# FPA.net
KiCad netlist of a schematic drawn in Altium Designer
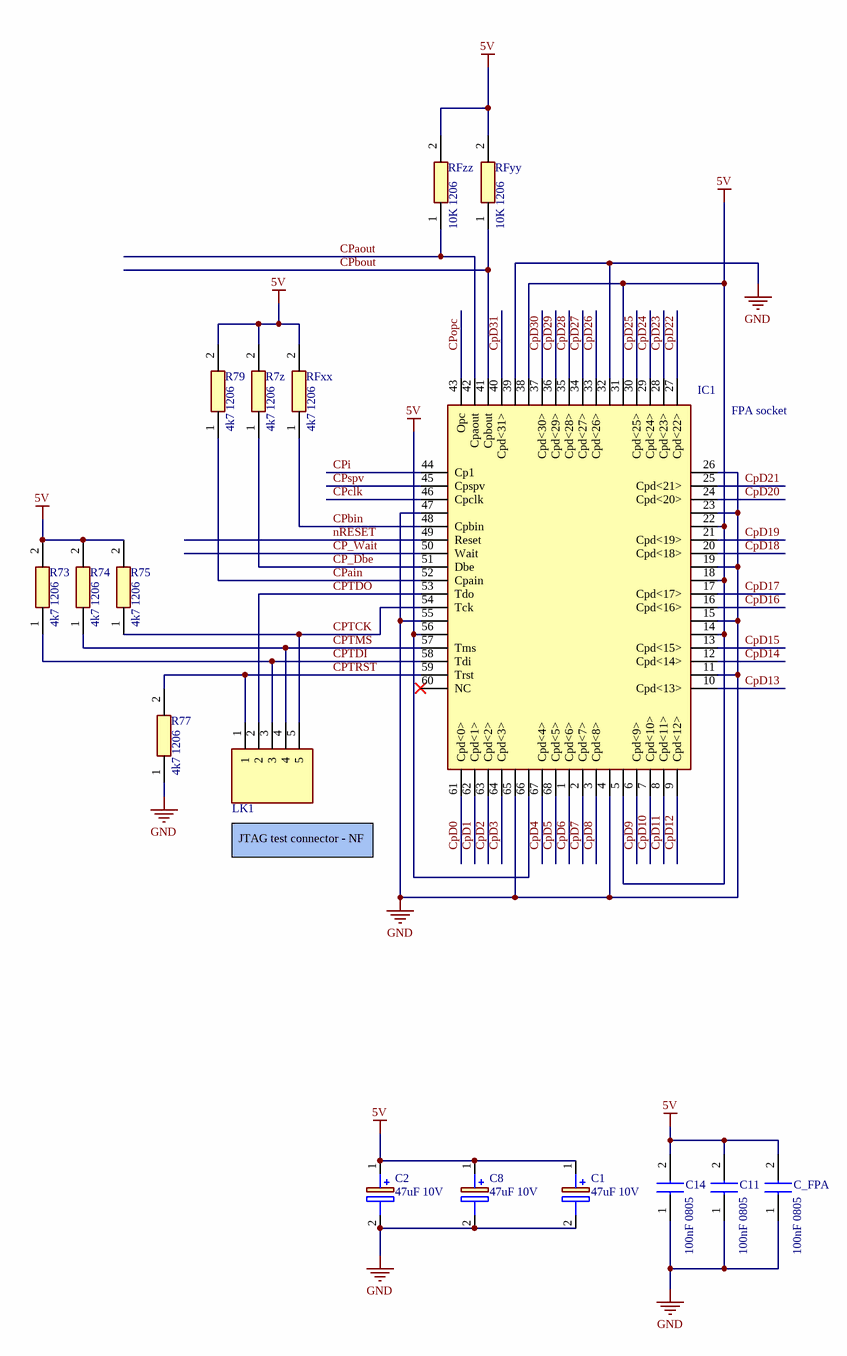
[diagram p0: FPA.SchDoc]

(export (version "E")
  (design (tool "Eeschema 10.0.6"))
  (components
    (comp (ref "C1")
      (value "47uF 10V")
      (footprint "SamacSys:CAPPA3500W50L1400D525")
      (description "Capacitor Polarised")
      (fields
        (field (name "MANUFACTURER_PART_NUMBER") "226TTA035MSD")
        (field (name "MOUSER PART NUMBER") "598-226TTA035MSD")
      )
      (libsource (lib "*") (part "226TTA035MSD"))
    )
    (comp (ref "C2")
      (value "47uF 10V")
      (footprint "SamacSys:CAPPA3500W50L1400D525")
      (description "Capacitor Polarised")
      (fields
        (field (name "MANUFACTURER_PART_NUMBER") "226TTA035MSD")
        (field (name "MOUSER PART NUMBER") "598-226TTA035MSD")
      )
      (libsource (lib "*") (part "226TTA035MSD"))
    )
    (comp (ref "C8")
      (value "47uF 10V")
      (footprint "SamacSys:CAPPA3500W50L1400D525")
      (description "Capacitor Polarised")
      (fields
        (field (name "MANUFACTURER_PART_NUMBER") "226TTA035MSD")
        (field (name "MOUSER PART NUMBER") "598-226TTA035MSD")
      )
      (libsource (lib "*") (part "226TTA035MSD"))
    )
    (comp (ref "C11")
      (value "100nF 0805")
      (footprint "SamacSys:CAPC2012X140N")
      (description "Capacitor")
      (fields
        (field (name "MANUFACTURER_PART_NUMBER") "C0805C104J4JACAUTO")
        (field (name "MOUSER PART NUMBER") "80-C0805C104J4JAUTO")
      )
      (libsource (lib "*") (part "C0805C104J4JACAUTO"))
    )
    (comp (ref "C14")
      (value "100nF 0805")
      (footprint "SamacSys:CAPC2012X140N")
      (description "Capacitor")
      (fields
        (field (name "MANUFACTURER_PART_NUMBER") "C0805C104J4JACAUTO")
        (field (name "MOUSER PART NUMBER") "80-C0805C104J4JAUTO")
      )
      (libsource (lib "*") (part "C0805C104J4JACAUTO"))
    )
    (comp (ref "C_FPA")
      (value "100nF 0805")
      (footprint "SamacSys:CAPC2012X140N")
      (description "Capacitor")
      (fields
        (field (name "MANUFACTURER_PART_NUMBER") "C0805C104J4JACAUTO")
        (field (name "MOUSER PART NUMBER") "80-C0805C104J4JAUTO")
      )
      (libsource (lib "*") (part "C0805C104J4JACAUTO"))
    )
    (comp (ref "IC1")
      (value "FPA socket")
      (footprint "PLCC68ATx")
      (fields
        (field (name "MANUFACTURER_PART_NUMBER") "8468-21B1-RK-TR")
        (field (name "MOUSER PART NUMBER") "517-8468-21B1-RK-TR")
      )
      (libsource (lib "Acorn") (part "FPA_SKT_THT"))
    )
    (comp (ref "LK1")
      (value "PREC005SAAN-RC")
      (footprint "SamacSys:HDRV5W64P0X254_1X5_1270X254X864P")
      (description "Connector")
      (libsource (lib "*") (part "PREC005SAAN-RC"))
    )
    (comp (ref "R7z")
      (value "4k7 1206")
      (footprint "SamacSys:ERJ8ENF1000V")
      (description "Resistor")
      (fields
        (field (name "MANUFACTURER_PART_NUMBER") "ERJ-8ENF4701V")
        (field (name "MOUSER PART NUMBER") "667-ERJ-8ENF4701V")
      )
      (libsource (lib "*") (part "ERJ-8ENF4701V"))
    )
    (comp (ref "R73")
      (value "4k7 1206")
      (footprint "SamacSys:ERJ8ENF1000V")
      (description "Resistor")
      (fields
        (field (name "MANUFACTURER_PART_NUMBER") "ERJ-8ENF4701V")
        (field (name "MOUSER PART NUMBER") "667-ERJ-8ENF4701V")
      )
      (libsource (lib "*") (part "ERJ-8ENF4701V"))
    )
    (comp (ref "R74")
      (value "4k7 1206")
      (footprint "SamacSys:ERJ8ENF1000V")
      (description "Resistor")
      (fields
        (field (name "MANUFACTURER_PART_NUMBER") "ERJ-8ENF4701V")
        (field (name "MOUSER PART NUMBER") "667-ERJ-8ENF4701V")
      )
      (libsource (lib "*") (part "ERJ-8ENF4701V"))
    )
    (comp (ref "R75")
      (value "4k7 1206")
      (footprint "SamacSys:ERJ8ENF1000V")
      (description "Resistor")
      (fields
        (field (name "MANUFACTURER_PART_NUMBER") "ERJ-8ENF4701V")
        (field (name "MOUSER PART NUMBER") "667-ERJ-8ENF4701V")
      )
      (libsource (lib "*") (part "ERJ-8ENF4701V"))
    )
    (comp (ref "R77")
      (value "4k7 1206")
      (footprint "SamacSys:ERJ8ENF1000V")
      (description "Resistor")
      (fields
        (field (name "MANUFACTURER_PART_NUMBER") "ERJ-8ENF4701V")
        (field (name "MOUSER PART NUMBER") "667-ERJ-8ENF4701V")
      )
      (libsource (lib "*") (part "ERJ-8ENF4701V"))
    )
    (comp (ref "R79")
      (value "4k7 1206")
      (footprint "SamacSys:ERJ8ENF1000V")
      (description "Resistor")
      (fields
        (field (name "MANUFACTURER_PART_NUMBER") "ERJ-8ENF4701V")
        (field (name "MOUSER PART NUMBER") "667-ERJ-8ENF4701V")
      )
      (libsource (lib "*") (part "ERJ-8ENF4701V"))
    )
    (comp (ref "RFxx")
      (value "4k7 1206")
      (footprint "SamacSys:ERJ8ENF1000V")
      (description "Resistor")
      (fields
        (field (name "MANUFACTURER_PART_NUMBER") "ERJ-8ENF4701V")
        (field (name "MOUSER PART NUMBER") "667-ERJ-8ENF4701V")
      )
      (libsource (lib "*") (part "ERJ-8ENF4701V"))
    )
    (comp (ref "RFyy")
      (value "10K 1206")
      (footprint "SamacSys:ERJUP8")
      (description "Resistor")
      (fields (field (name "MANUFACTURER_PART_NUMBER") "ERJ-UP8D1002V"))
      (libsource (lib "*") (part "ERJ-UP8D1002V"))
    )
    (comp (ref "RFzz")
      (value "10K 1206")
      (footprint "SamacSys:ERJUP8")
      (description "Resistor")
      (fields (field (name "MANUFACTURER_PART_NUMBER") "ERJ-UP8D1002V"))
      (libsource (lib "*") (part "ERJ-UP8D1002V"))
    )
  )
  (nets
    (net (code "1") (name "/CPTCK") (class "Default")
      (node (ref "IC1") (pin "54") (pinfunction "Tck_54") (pintype "passive"))
      (node (ref "LK1") (pin "5") (pinfunction "5_5") (pintype "passive"))
      (node (ref "R75") (pin "1") (pinfunction "1_1") (pintype "passive"))
    )
    (net (code "2") (name "/CPTDI") (class "Default")
      (node (ref "IC1") (pin "58") (pinfunction "Tdi_58") (pintype "passive"))
      (node (ref "LK1") (pin "3") (pinfunction "3_3") (pintype "passive"))
      (node (ref "R73") (pin "1") (pinfunction "1_1") (pintype "passive"))
    )
    (net (code "3") (name "/CPTDO") (class "Default")
      (node (ref "IC1") (pin "53") (pinfunction "Tdo_53") (pintype "passive"))
      (node (ref "LK1") (pin "2") (pinfunction "2_2") (pintype "passive"))
    )
    (net (code "4") (name "/CPTMS") (class "Default")
      (node (ref "IC1") (pin "57") (pinfunction "Tms_57") (pintype "passive"))
      (node (ref "LK1") (pin "4") (pinfunction "4_4") (pintype "passive"))
      (node (ref "R74") (pin "1") (pinfunction "1_1") (pintype "passive"))
    )
    (net (code "5") (name "/CPTRST") (class "Default")
      (node (ref "IC1") (pin "59") (pinfunction "Trst_59") (pintype "passive"))
      (node (ref "LK1") (pin "1") (pinfunction "1_1") (pintype "passive"))
      (node (ref "R77") (pin "2") (pinfunction "2_2") (pintype "passive"))
    )
    (net (code "6") (name "/CP_Dbe") (class "Default")
      (node (ref "IC1") (pin "51") (pinfunction "Dbe_51") (pintype "passive"))
      (node (ref "R7z") (pin "1") (pinfunction "1_1") (pintype "passive"))
    )
    (net (code "7") (name "/CP_Wait") (class "Default")
      (node (ref "IC1") (pin "50") (pinfunction "Wait_50") (pintype "passive"))
    )
    (net (code "8") (name "/CPain") (class "Default")
      (node (ref "IC1") (pin "52") (pinfunction "Cpain_52") (pintype "passive"))
      (node (ref "R79") (pin "1") (pinfunction "1_1") (pintype "passive"))
    )
    (net (code "9") (name "/CPaout") (class "Default")
      (node (ref "IC1") (pin "42") (pinfunction "Cpaout_42") (pintype "passive"))
      (node (ref "RFzz") (pin "1") (pinfunction "1_1") (pintype "passive"))
    )
    (net (code "10") (name "/CPbin") (class "Default")
      (node (ref "IC1") (pin "48") (pinfunction "Cpbin_48") (pintype "passive"))
      (node (ref "RFxx") (pin "1") (pinfunction "1_1") (pintype "passive"))
    )
    (net (code "11") (name "/CPbout") (class "Default")
      (node (ref "IC1") (pin "41") (pinfunction "Cpbout_41") (pintype "passive"))
      (node (ref "RFyy") (pin "1") (pinfunction "1_1") (pintype "passive"))
    )
    (net (code "12") (name "/CPclk") (class "Default")
      (node (ref "IC1") (pin "46") (pinfunction "Cpclk_46") (pintype "passive"))
    )
    (net (code "13") (name "/CPi") (class "Default")
      (node (ref "IC1") (pin "44") (pinfunction "Cp1_44") (pintype "passive"))
    )
    (net (code "14") (name "/CPopc") (class "Default")
      (node (ref "IC1") (pin "43") (pinfunction "Opc_43") (pintype "passive"))
    )
    (net (code "15") (name "/CPspv") (class "Default")
      (node (ref "IC1") (pin "45") (pinfunction "Cpspv_45") (pintype "passive"))
    )
    (net (code "16") (name "/CpD0") (class "Default")
      (node (ref "IC1") (pin "61") (pinfunction "Cpd<0>_61") (pintype "passive"))
    )
    (net (code "17") (name "/CpD1") (class "Default")
      (node (ref "IC1") (pin "62") (pinfunction "Cpd<1>_62") (pintype "passive"))
    )
    (net (code "18") (name "/CpD2") (class "Default")
      (node (ref "IC1") (pin "63") (pinfunction "Cpd<2>_63") (pintype "passive"))
    )
    (net (code "19") (name "/CpD3") (class "Default")
      (node (ref "IC1") (pin "64") (pinfunction "Cpd<3>_64") (pintype "passive"))
    )
    (net (code "20") (name "/CpD4") (class "Default")
      (node (ref "IC1") (pin "67") (pinfunction "Cpd<4>_67") (pintype "passive"))
    )
    (net (code "21") (name "/CpD5") (class "Default")
      (node (ref "IC1") (pin "68") (pinfunction "Cpd<5>_68") (pintype "passive"))
    )
    (net (code "22") (name "/CpD6") (class "Default")
      (node (ref "IC1") (pin "1") (pinfunction "Cpd<6>_1") (pintype "passive"))
    )
    (net (code "23") (name "/CpD7") (class "Default")
      (node (ref "IC1") (pin "2") (pinfunction "Cpd<7>_2") (pintype "passive"))
    )
    (net (code "24") (name "/CpD8") (class "Default")
      (node (ref "IC1") (pin "3") (pinfunction "Cpd<8>_3") (pintype "passive"))
    )
    (net (code "25") (name "/CpD9") (class "Default")
      (node (ref "IC1") (pin "6") (pinfunction "Cpd<9>_6") (pintype "passive"))
    )
    (net (code "26") (name "/CpD10") (class "Default")
      (node (ref "IC1") (pin "7") (pinfunction "Cpd<10>_7") (pintype "passive"))
    )
    (net (code "27") (name "/CpD11") (class "Default")
      (node (ref "IC1") (pin "8") (pinfunction "Cpd<11>_8") (pintype "passive"))
    )
    (net (code "28") (name "/CpD12") (class "Default")
      (node (ref "IC1") (pin "9") (pinfunction "Cpd<12>_9") (pintype "passive"))
    )
    (net (code "29") (name "/CpD13") (class "Default")
      (node (ref "IC1") (pin "10") (pinfunction "Cpd<13>_10") (pintype "passive"))
    )
    (net (code "30") (name "/CpD14") (class "Default")
      (node (ref "IC1") (pin "12") (pinfunction "Cpd<14>_12") (pintype "passive"))
    )
    (net (code "31") (name "/CpD15") (class "Default")
      (node (ref "IC1") (pin "13") (pinfunction "Cpd<15>_13") (pintype "passive"))
    )
    (net (code "32") (name "/CpD16") (class "Default")
      (node (ref "IC1") (pin "16") (pinfunction "Cpd<16>_16") (pintype "passive"))
    )
    (net (code "33") (name "/CpD17") (class "Default")
      (node (ref "IC1") (pin "17") (pinfunction "Cpd<17>_17") (pintype "passive"))
    )
    (net (code "34") (name "/CpD18") (class "Default")
      (node (ref "IC1") (pin "20") (pinfunction "Cpd<18>_20") (pintype "passive"))
    )
    (net (code "35") (name "/CpD19") (class "Default")
      (node (ref "IC1") (pin "21") (pinfunction "Cpd<19>_21") (pintype "passive"))
    )
    (net (code "36") (name "/CpD20") (class "Default")
      (node (ref "IC1") (pin "24") (pinfunction "Cpd<20>_24") (pintype "passive"))
    )
    (net (code "37") (name "/CpD21") (class "Default")
      (node (ref "IC1") (pin "25") (pinfunction "Cpd<21>_25") (pintype "passive"))
    )
    (net (code "38") (name "/CpD22") (class "Default")
      (node (ref "IC1") (pin "27") (pinfunction "Cpd<22>_27") (pintype "passive"))
    )
    (net (code "39") (name "/CpD23") (class "Default")
      (node (ref "IC1") (pin "28") (pinfunction "Cpd<23>_28") (pintype "passive"))
    )
    (net (code "40") (name "/CpD24") (class "Default")
      (node (ref "IC1") (pin "29") (pinfunction "Cpd<24>_29") (pintype "passive"))
    )
    (net (code "41") (name "/CpD25") (class "Default")
      (node (ref "IC1") (pin "30") (pinfunction "Cpd<25>_30") (pintype "passive"))
    )
    (net (code "42") (name "/CpD26") (class "Default")
      (node (ref "IC1") (pin "33") (pinfunction "Cpd<26>_33") (pintype "passive"))
    )
    (net (code "43") (name "/CpD27") (class "Default")
      (node (ref "IC1") (pin "34") (pinfunction "Cpd<27>_34") (pintype "passive"))
    )
    (net (code "44") (name "/CpD28") (class "Default")
      (node (ref "IC1") (pin "35") (pinfunction "Cpd<28>_35") (pintype "passive"))
    )
    (net (code "45") (name "/CpD29") (class "Default")
      (node (ref "IC1") (pin "36") (pinfunction "Cpd<29>_36") (pintype "passive"))
    )
    (net (code "46") (name "/CpD30") (class "Default")
      (node (ref "IC1") (pin "37") (pinfunction "Cpd<30>_37") (pintype "passive"))
    )
    (net (code "47") (name "/CpD31") (class "Default")
      (node (ref "IC1") (pin "40") (pinfunction "Cpd<31>_40") (pintype "passive"))
    )
    (net (code "48") (name "/nRESET") (class "Default")
      (node (ref "IC1") (pin "49") (pinfunction "Reset_49") (pintype "passive"))
    )
    (net (code "49") (name "5V") (class "Default")
      (node (ref "C1") (pin "1") (pinfunction "+_1") (pintype "passive"))
      (node (ref "C11") (pin "2") (pinfunction "2_2") (pintype "passive"))
      (node (ref "C14") (pin "2") (pinfunction "2_2") (pintype "passive"))
      (node (ref "C2") (pin "1") (pinfunction "+_1") (pintype "passive"))
      (node (ref "C8") (pin "1") (pinfunction "+_1") (pintype "passive"))
      (node (ref "C_FPA") (pin "2") (pinfunction "2_2") (pintype "passive"))
      (node (ref "IC1") (pin "14") (pintype "passive"))
      (node (ref "IC1") (pin "18") (pintype "passive"))
      (node (ref "IC1") (pin "22") (pintype "passive"))
      (node (ref "IC1") (pin "31") (pintype "passive"))
      (node (ref "IC1") (pin "38") (pintype "passive"))
      (node (ref "IC1") (pin "5") (pintype "passive"))
      (node (ref "IC1") (pin "56") (pintype "passive"))
      (node (ref "IC1") (pin "66") (pintype "passive"))
      (node (ref "R73") (pin "2") (pinfunction "2_2") (pintype "passive"))
      (node (ref "R74") (pin "2") (pinfunction "2_2") (pintype "passive"))
      (node (ref "R75") (pin "2") (pinfunction "2_2") (pintype "passive"))
      (node (ref "R79") (pin "2") (pinfunction "2_2") (pintype "passive"))
      (node (ref "R7z") (pin "2") (pinfunction "2_2") (pintype "passive"))
      (node (ref "RFxx") (pin "2") (pinfunction "2_2") (pintype "passive"))
      (node (ref "RFyy") (pin "2") (pinfunction "2_2") (pintype "passive"))
      (node (ref "RFzz") (pin "2") (pinfunction "2_2") (pintype "passive"))
    )
    (net (code "50") (name "GND") (class "Default")
      (node (ref "C1") (pin "2") (pinfunction "-_2") (pintype "passive"))
      (node (ref "C11") (pin "1") (pinfunction "1_1") (pintype "passive"))
      (node (ref "C14") (pin "1") (pinfunction "1_1") (pintype "passive"))
      (node (ref "C2") (pin "2") (pinfunction "-_2") (pintype "passive"))
      (node (ref "C8") (pin "2") (pinfunction "-_2") (pintype "passive"))
      (node (ref "C_FPA") (pin "1") (pinfunction "1_1") (pintype "passive"))
      (node (ref "IC1") (pin "11") (pintype "passive"))
      (node (ref "IC1") (pin "15") (pintype "passive"))
      (node (ref "IC1") (pin "19") (pintype "passive"))
      (node (ref "IC1") (pin "23") (pintype "passive"))
      (node (ref "IC1") (pin "26") (pintype "passive"))
      (node (ref "IC1") (pin "32") (pintype "passive"))
      (node (ref "IC1") (pin "39") (pintype "passive"))
      (node (ref "IC1") (pin "4") (pintype "passive"))
      (node (ref "IC1") (pin "47") (pintype "passive"))
      (node (ref "IC1") (pin "55") (pintype "passive"))
      (node (ref "IC1") (pin "65") (pintype "passive"))
      (node (ref "R77") (pin "1") (pinfunction "1_1") (pintype "passive"))
    )
    (net (code "51") (name "unconnected-(IC1-NC-Pad60)") (class "Default")
      (node (ref "IC1") (pin "60") (pinfunction "NC_60") (pintype "passive+no_connect"))
    )
  )
)
